# main.net
KiCad netlist of a schematic drawn in Altium Designer
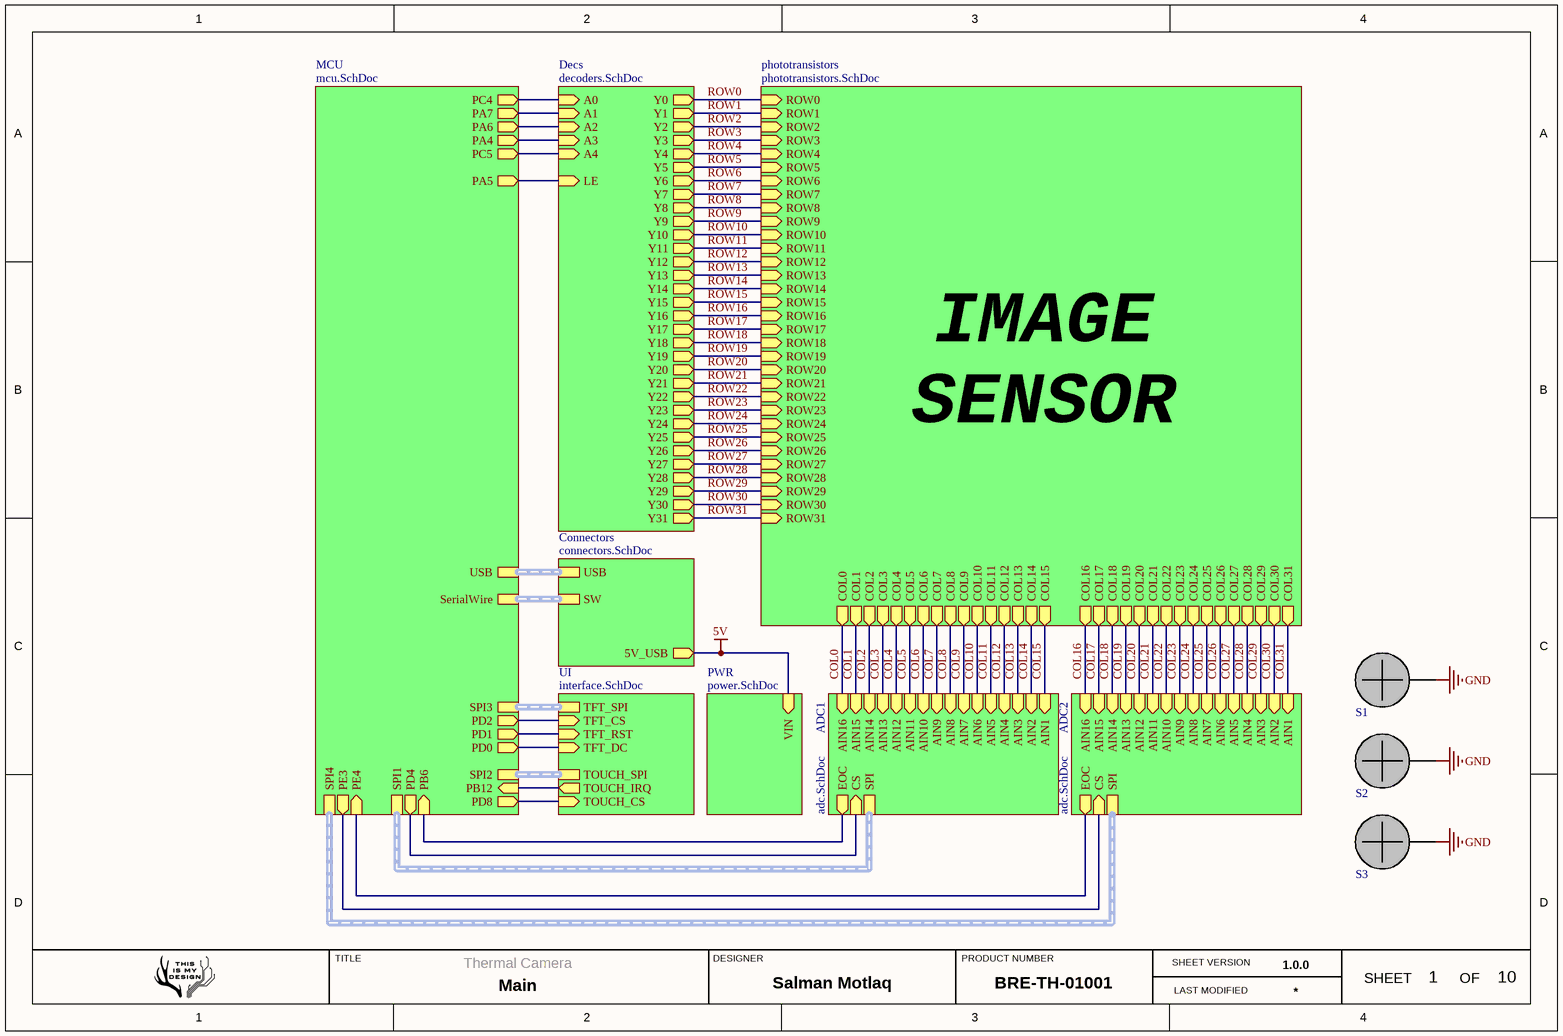
[diagram p0: main.SchDoc]

(export (version "E")
  (design (tool "Eeschema 10.0.6"))
  (components
    (comp (ref "S1") (value "Screw") (footprint "M3") (libsource (lib "BayanLib") (part "Screw")))
    (comp (ref "S2") (value "Screw") (footprint "M3") (libsource (lib "BayanLib") (part "Screw")))
    (comp (ref "S3") (value "Screw") (footprint "M3") (libsource (lib "BayanLib") (part "Screw")))
  )
  (nets
    (net (code "87") (name "GND") (class "Default")
      (node (ref "S1") (pin "0") (pinfunction "0_0") (pintype "passive"))
      (node (ref "S2") (pin "0") (pinfunction "0_0") (pintype "passive"))
      (node (ref "S3") (pin "0") (pinfunction "0_0") (pintype "passive"))
    )
  )
)
